# MIC.net
KiCad netlist of a schematic drawn in EasyEDA Pro
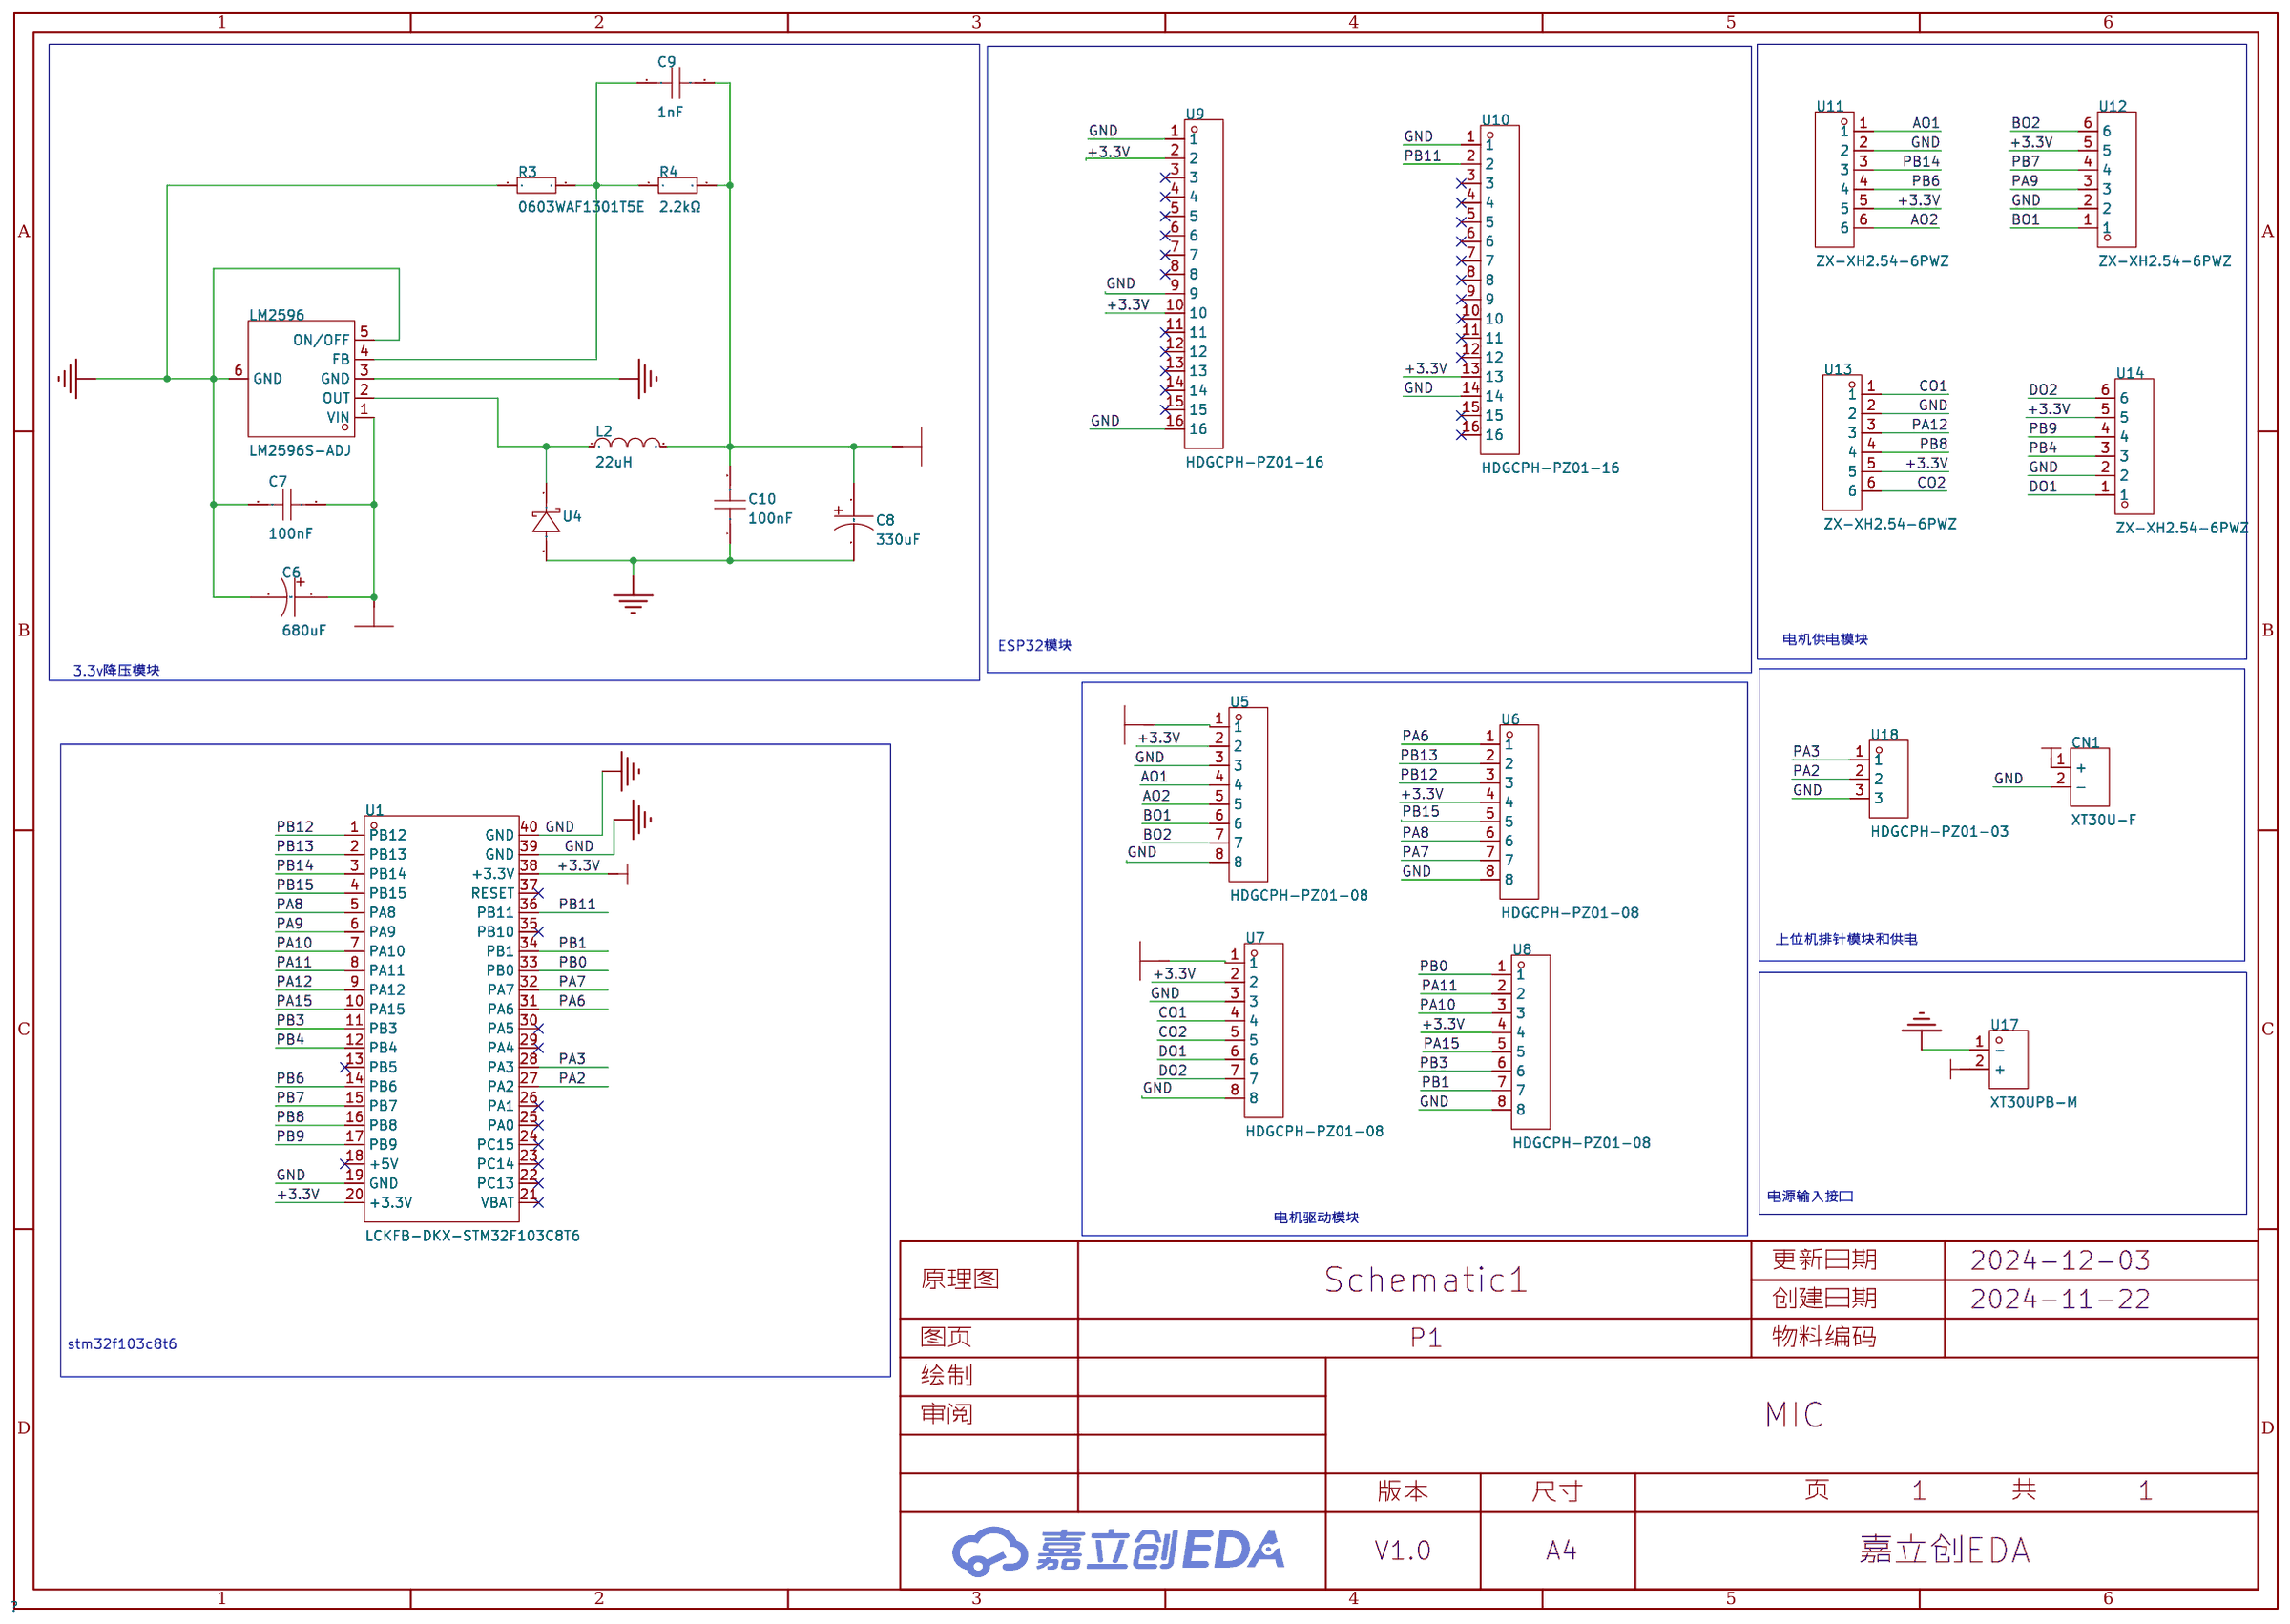
[diagram p0: schematic sheet]

(export (version "E")
  (design (tool "Eeschema 10.0.6"))
  (components
    (comp (ref "C6")
      (value "680uF")
      (footprint "easyedapro:CAP-TH_BD10.0-P5.00-D1.0-FD")
      (fields (field (name "Manufacturer Part") "LKME1601V681MF") (field (name "Manufacturer") "Ymin(永铭)"))
      (libsource (lib "easyedapro") (part "LKME1601V681MF"))
    )
    (comp (ref "C7")
      (value "100nF")
      (footprint "easyedapro:C0805")
      (fields
        (field (name "Manufacturer Part") "CC0805KKX7R0BB104")
        (field (name "Manufacturer") "YAGEO(国巨)")
      )
      (libsource (lib "easyedapro") (part "CapAcitance"))
    )
    (comp (ref "C8")
      (value "330uF")
      (footprint "easyedapro:CAP-TH_BD10.0-P5.00-D1.0-FD")
      (fields (field (name "Manufacturer Part") "ERE1HM331G16OT") (field (name "Manufacturer") "AISHI(艾华集团)"))
      (libsource (lib "easyedapro") (part "LKME1601V681MF"))
    )
    (comp (ref "C9")
      (value "1nF")
      (footprint "easyedapro:C0805")
      (fields
        (field (name "Manufacturer Part") "CL10B102KB8NNNC")
        (field (name "Manufacturer") "SAMSUNG(三星)")
      )
      (libsource (lib "easyedapro") (part "CapAcitance"))
    )
    (comp (ref "C10")
      (value "100nF")
      (footprint "easyedapro:C0805")
      (fields
        (field (name "Manufacturer Part") "CC0603KRX7R9BB104")
        (field (name "Manufacturer") "YAGEO(国巨)")
      )
      (libsource (lib "easyedapro") (part "CapAcitance"))
    )
    (comp (ref "CN1")
      (value "XT30U-F")
      (footprint "easyedapro:CONN-TH_XT30UPB-F")
      (description "类别:-;类型1:-;")
      (fields (field (name "Manufacturer") "AMASS(艾迈斯)"))
      (libsource (lib "easyedapro") (part "XT30UPB-F"))
    )
    (comp (ref "L2")
      (value "22uH")
      (footprint "easyedapro:IND-SMD_L7.0-W6.6_FXL0630")
      (description "电感值:22uH;精度:±20%;额定电流:2.5A;饱和电流(Isat):3A;类型:一体成型电感;")
      (fields (field (name "Manufacturer Part") "SMMS0630-220M") (field (name "Manufacturer") "SXN(顺翔诺)"))
      (libsource (lib "easyedapro") (part "FXL0630-220-M"))
    )
    (comp (ref "LM2596")
      (value "LM2596S-ADJ")
      (footprint "easyedapro:TO-263-5_L10.0-W8.4-P1.70-LS15.3-BR")
      (description "功能类型:降压型;输出类型:可调;输入电压:40V;输出电压:1.23V~37V;输出电流(最大值):3.5A;")
      (fields (field (name "Manufacturer") "HXY MOSFET(华轩阳电子)"))
      (libsource (lib "easyedapro") (part "LM2596S-ADJ_C5349987"))
    )
    (comp (ref "R3")
      (value "0603WAF1301T5E")
      (footprint "easyedapro:R0603")
      (fields (field (name "Manufacturer") "UNI-ROYAL(厚声)"))
      (libsource (lib "easyedapro") (part "电阻"))
    )
    (comp (ref "R4")
      (value "2.2kΩ")
      (footprint "easyedapro:R0603")
      (fields (field (name "Manufacturer Part") "RC0603JR-072K2L") (field (name "Manufacturer") "YAGEO(国巨)"))
      (libsource (lib "easyedapro") (part "电阻"))
    )
    (comp (ref "U1")
      (value "LCKFB-DKX-STM32F103C8T6")
      (footprint "easyedapro:CONN-TH_L53.3-W22.9_STM32F103C8T6-CARD")
      (fields (field (name "Manufacturer") "立创开发板"))
      (libsource (lib "easyedapro") (part "LCKFB-DKX-STM32F103C8T6"))
    )
    (comp (ref "U4")
      (value "CDBC540-G")
      (footprint "easyedapro:SMC_L6.9-W5.9-LS7.9-RD")
      (description "正向压降(Vf):550mV@5A;直流反向耐压(Vr):40V;平均整流电流(Io):5A;")
      (fields (field (name "Manufacturer") "Comchip(典琦)"))
      (libsource (lib "easyedapro") (part "cdbc540-g"))
    )
    (comp (ref "U5")
      (value "HDGCPH-PZ01-08")
      (footprint "easyedapro:HDR-TH_8P-P2.54-V-M")
      (fields (field (name "Manufacturer") "HDGC(华德共创)"))
      (libsource (lib "easyedapro") (part "HDGCPH-PZ01- 08"))
    )
    (comp (ref "U6")
      (value "HDGCPH-PZ01-08")
      (footprint "easyedapro:HDR-TH_8P-P2.54-V-M")
      (fields (field (name "Manufacturer") "HDGC(华德共创)"))
      (libsource (lib "easyedapro") (part "HDGCPH-PZ01- 08"))
    )
    (comp (ref "U7")
      (value "HDGCPH-PZ01-08")
      (footprint "easyedapro:HDR-TH_8P-P2.54-V-M")
      (fields (field (name "Manufacturer") "HDGC(华德共创)"))
      (libsource (lib "easyedapro") (part "HDGCPH-PZ01- 08"))
    )
    (comp (ref "U8")
      (value "HDGCPH-PZ01-08")
      (footprint "easyedapro:HDR-TH_8P-P2.54-V-M")
      (fields (field (name "Manufacturer") "HDGC(华德共创)"))
      (libsource (lib "easyedapro") (part "HDGCPH-PZ01- 08"))
    )
    (comp (ref "U9")
      (value "HDGCPH-PZ01-16")
      (footprint "easyedapro:HDR-TH_16P-P2.54-V-M_1")
      (fields (field (name "Manufacturer") "HDGC(华德共创)"))
      (libsource (lib "easyedapro") (part "HDGCPH-PZ01-16"))
    )
    (comp (ref "U10")
      (value "HDGCPH-PZ01-16")
      (footprint "easyedapro:HDR-TH_16P-P2.54-V-M_1")
      (fields (field (name "Manufacturer") "HDGC(华德共创)"))
      (libsource (lib "easyedapro") (part "HDGCPH-PZ01-16"))
    )
    (comp (ref "U11")
      (value "ZX-XH2.54-6PWZ")
      (footprint "easyedapro:CONN-TH_6P-P2.50_ZX-XH2.54-6PWZ")
      (fields (field (name "Manufacturer") "Megastar(兆星)"))
      (libsource (lib "easyedapro") (part "ZX-XH2.54-6PWZ"))
    )
    (comp (ref "U12")
      (value "ZX-XH2.54-6PWZ")
      (footprint "easyedapro:CONN-TH_6P-P2.50_ZX-XH2.54-6PWZ")
      (fields (field (name "Manufacturer") "Megastar(兆星)"))
      (libsource (lib "easyedapro") (part "ZX-XH2.54-6PWZ"))
    )
    (comp (ref "U13")
      (value "ZX-XH2.54-6PWZ")
      (footprint "easyedapro:CONN-TH_6P-P2.50_ZX-XH2.54-6PWZ")
      (fields (field (name "Manufacturer") "Megastar(兆星)"))
      (libsource (lib "easyedapro") (part "ZX-XH2.54-6PWZ"))
    )
    (comp (ref "U14")
      (value "ZX-XH2.54-6PWZ")
      (footprint "easyedapro:CONN-TH_6P-P2.50_ZX-XH2.54-6PWZ")
      (fields (field (name "Manufacturer") "Megastar(兆星)"))
      (libsource (lib "easyedapro") (part "ZX-XH2.54-6PWZ"))
    )
    (comp (ref "U17")
      (value "XT30UPB-M")
      (footprint "easyedapro:CONN-TH_XT30U-F")
      (description "类别:-;类型1:-;")
      (fields (field (name "Manufacturer") "AMASS(艾迈斯)"))
      (libsource (lib "easyedapro") (part "XT30U-F"))
    )
    (comp (ref "U18")
      (value "HDGCPH-PZ01-03")
      (footprint "easyedapro:HDR-TH_3P-P2.54-V-M-3")
      (fields (field (name "Manufacturer") "HDGC(华德共创)"))
      (libsource (lib "easyedapro") (part "HDGCPH-PZ01-03"))
    )
  )
  (nets
    (net (code "1") (name "+3.3V") (class "Default")
      (node (ref "C10") (pin "2") (pinfunction "2_2") (pintype "input"))
      (node (ref "C8") (pin "1") (pinfunction "1_1") (pintype "input"))
      (node (ref "C9") (pin "2") (pinfunction "2_2") (pintype "input"))
      (node (ref "L2") (pin "2") (pinfunction "2_2") (pintype "unspecified"))
      (node (ref "R4") (pin "2") (pinfunction "2_2") (pintype "input"))
      (node (ref "U1") (pin "20") (pinfunction "+3.3V_20") (pintype "unspecified"))
      (node (ref "U1") (pin "38") (pinfunction "+3.3V_38") (pintype "unspecified"))
      (node (ref "U10") (pin "13") (pinfunction "13_13") (pintype "unspecified"))
      (node (ref "U11") (pin "5") (pinfunction "5_5") (pintype "unspecified"))
      (node (ref "U12") (pin "5") (pinfunction "5_5") (pintype "unspecified"))
      (node (ref "U13") (pin "5") (pinfunction "5_5") (pintype "unspecified"))
      (node (ref "U14") (pin "5") (pinfunction "5_5") (pintype "unspecified"))
      (node (ref "U5") (pin "2") (pinfunction "2_2") (pintype "unspecified"))
      (node (ref "U6") (pin "4") (pinfunction "4_4") (pintype "unspecified"))
      (node (ref "U7") (pin "2") (pinfunction "2_2") (pintype "unspecified"))
      (node (ref "U8") (pin "4") (pinfunction "4_4") (pintype "unspecified"))
      (node (ref "U9") (pin "10") (pinfunction "10_10") (pintype "unspecified"))
      (node (ref "U9") (pin "2") (pinfunction "2_2") (pintype "unspecified"))
    )
    (net (code "2") (name "+12V") (class "Default")
      (node (ref "C6") (pin "1") (pinfunction "1_1") (pintype "input"))
      (node (ref "C7") (pin "2") (pinfunction "2_2") (pintype "input"))
      (node (ref "CN1") (pin "1") (pinfunction "+_1") (pintype "unspecified"))
      (node (ref "LM2596") (pin "1") (pinfunction "VIN_1") (pintype "unspecified"))
      (node (ref "U17") (pin "2") (pinfunction "+_2") (pintype "unspecified"))
      (node (ref "U5") (pin "1") (pinfunction "1_1") (pintype "unspecified"))
      (node (ref "U7") (pin "1") (pinfunction "1_1") (pintype "unspecified"))
    )
    (net (code "3") (name "/AO1") (class "Default")
      (node (ref "U11") (pin "1") (pinfunction "1_1") (pintype "unspecified"))
      (node (ref "U5") (pin "4") (pinfunction "4_4") (pintype "unspecified"))
    )
    (net (code "4") (name "/AO2") (class "Default")
      (node (ref "U11") (pin "6") (pinfunction "6_6") (pintype "unspecified"))
      (node (ref "U5") (pin "5") (pinfunction "5_5") (pintype "unspecified"))
    )
    (net (code "5") (name "/BO1") (class "Default")
      (node (ref "U12") (pin "1") (pinfunction "1_1") (pintype "unspecified"))
      (node (ref "U5") (pin "6") (pinfunction "6_6") (pintype "unspecified"))
    )
    (net (code "6") (name "/BO2") (class "Default")
      (node (ref "U12") (pin "6") (pinfunction "6_6") (pintype "unspecified"))
      (node (ref "U5") (pin "7") (pinfunction "7_7") (pintype "unspecified"))
    )
    (net (code "7") (name "/CO1") (class "Default")
      (node (ref "U13") (pin "1") (pinfunction "1_1") (pintype "unspecified"))
      (node (ref "U7") (pin "4") (pinfunction "4_4") (pintype "unspecified"))
    )
    (net (code "8") (name "/CO2") (class "Default")
      (node (ref "U13") (pin "6") (pinfunction "6_6") (pintype "unspecified"))
      (node (ref "U7") (pin "5") (pinfunction "5_5") (pintype "unspecified"))
    )
    (net (code "9") (name "/DO1") (class "Default")
      (node (ref "U14") (pin "1") (pinfunction "1_1") (pintype "unspecified"))
      (node (ref "U7") (pin "6") (pinfunction "6_6") (pintype "unspecified"))
    )
    (net (code "10") (name "/DO2") (class "Default")
      (node (ref "U14") (pin "6") (pinfunction "6_6") (pintype "unspecified"))
      (node (ref "U7") (pin "7") (pinfunction "7_7") (pintype "unspecified"))
    )
    (net (code "11") (name "/PA2") (class "Default")
      (node (ref "U1") (pin "27") (pinfunction "PA2_27") (pintype "unspecified"))
      (node (ref "U18") (pin "2") (pinfunction "2_2") (pintype "unspecified"))
    )
    (net (code "12") (name "/PA3") (class "Default")
      (node (ref "U1") (pin "28") (pinfunction "PA3_28") (pintype "unspecified"))
      (node (ref "U18") (pin "1") (pinfunction "1_1") (pintype "unspecified"))
    )
    (net (code "13") (name "/PA6") (class "Default")
      (node (ref "U1") (pin "31") (pinfunction "PA6_31") (pintype "unspecified"))
      (node (ref "U6") (pin "1") (pinfunction "1_1") (pintype "unspecified"))
    )
    (net (code "14") (name "/PA7") (class "Default")
      (node (ref "U1") (pin "32") (pinfunction "PA7_32") (pintype "unspecified"))
      (node (ref "U6") (pin "7") (pinfunction "7_7") (pintype "unspecified"))
    )
    (net (code "15") (name "/PA8") (class "Default")
      (node (ref "U1") (pin "5") (pinfunction "PA8_5") (pintype "unspecified"))
      (node (ref "U6") (pin "6") (pinfunction "6_6") (pintype "unspecified"))
    )
    (net (code "16") (name "/PA9") (class "Default")
      (node (ref "U1") (pin "6") (pinfunction "PA9_6") (pintype "unspecified"))
      (node (ref "U12") (pin "3") (pinfunction "3_3") (pintype "unspecified"))
    )
    (net (code "17") (name "/PA10") (class "Default")
      (node (ref "U1") (pin "7") (pinfunction "PA10_7") (pintype "unspecified"))
      (node (ref "U8") (pin "3") (pinfunction "3_3") (pintype "unspecified"))
    )
    (net (code "18") (name "/PA11") (class "Default")
      (node (ref "U1") (pin "8") (pinfunction "PA11_8") (pintype "unspecified"))
      (node (ref "U8") (pin "2") (pinfunction "2_2") (pintype "unspecified"))
    )
    (net (code "19") (name "/PA12") (class "Default")
      (node (ref "U1") (pin "9") (pinfunction "PA12_9") (pintype "unspecified"))
      (node (ref "U13") (pin "3") (pinfunction "3_3") (pintype "unspecified"))
    )
    (net (code "20") (name "/PA15") (class "Default")
      (node (ref "U1") (pin "10") (pinfunction "PA15_10") (pintype "unspecified"))
      (node (ref "U8") (pin "5") (pinfunction "5_5") (pintype "unspecified"))
    )
    (net (code "21") (name "/PB0") (class "Default")
      (node (ref "U1") (pin "33") (pinfunction "PB0_33") (pintype "unspecified"))
      (node (ref "U8") (pin "1") (pinfunction "1_1") (pintype "unspecified"))
    )
    (net (code "22") (name "/PB1") (class "Default")
      (node (ref "U1") (pin "34") (pinfunction "PB1_34") (pintype "unspecified"))
      (node (ref "U8") (pin "7") (pinfunction "7_7") (pintype "unspecified"))
    )
    (net (code "23") (name "/PB3") (class "Default")
      (node (ref "U1") (pin "11") (pinfunction "PB3_11") (pintype "unspecified"))
      (node (ref "U8") (pin "6") (pinfunction "6_6") (pintype "unspecified"))
    )
    (net (code "24") (name "/PB4") (class "Default")
      (node (ref "U1") (pin "12") (pinfunction "PB4_12") (pintype "unspecified"))
      (node (ref "U14") (pin "3") (pinfunction "3_3") (pintype "unspecified"))
    )
    (net (code "25") (name "/PB6") (class "Default")
      (node (ref "U1") (pin "14") (pinfunction "PB6_14") (pintype "unspecified"))
      (node (ref "U11") (pin "4") (pinfunction "4_4") (pintype "unspecified"))
    )
    (net (code "26") (name "/PB7") (class "Default")
      (node (ref "U1") (pin "15") (pinfunction "PB7_15") (pintype "unspecified"))
      (node (ref "U12") (pin "4") (pinfunction "4_4") (pintype "unspecified"))
    )
    (net (code "27") (name "/PB8") (class "Default")
      (node (ref "U1") (pin "16") (pinfunction "PB8_16") (pintype "unspecified"))
      (node (ref "U13") (pin "4") (pinfunction "4_4") (pintype "unspecified"))
    )
    (net (code "28") (name "/PB9") (class "Default")
      (node (ref "U1") (pin "17") (pinfunction "PB9_17") (pintype "unspecified"))
      (node (ref "U14") (pin "4") (pinfunction "4_4") (pintype "unspecified"))
    )
    (net (code "29") (name "/PB11") (class "Default")
      (node (ref "U1") (pin "36") (pinfunction "PB11_36") (pintype "unspecified"))
      (node (ref "U10") (pin "2") (pinfunction "2_2") (pintype "unspecified"))
    )
    (net (code "30") (name "/PB12") (class "Default")
      (node (ref "U1") (pin "1") (pinfunction "PB12_1") (pintype "unspecified"))
      (node (ref "U6") (pin "3") (pinfunction "3_3") (pintype "unspecified"))
    )
    (net (code "31") (name "/PB13") (class "Default")
      (node (ref "U1") (pin "2") (pinfunction "PB13_2") (pintype "unspecified"))
      (node (ref "U6") (pin "2") (pinfunction "2_2") (pintype "unspecified"))
    )
    (net (code "32") (name "/PB14") (class "Default")
      (node (ref "U1") (pin "3") (pinfunction "PB14_3") (pintype "unspecified"))
      (node (ref "U11") (pin "3") (pinfunction "3_3") (pintype "unspecified"))
    )
    (net (code "33") (name "/PB15") (class "Default")
      (node (ref "U1") (pin "4") (pinfunction "PB15_4") (pintype "unspecified"))
      (node (ref "U6") (pin "5") (pinfunction "5_5") (pintype "unspecified"))
    )
    (net (code "34") (name "GND") (class "Default")
      (node (ref "C10") (pin "1") (pinfunction "1_1") (pintype "input"))
      (node (ref "C6") (pin "2") (pinfunction "2_2") (pintype "input"))
      (node (ref "C7") (pin "1") (pinfunction "1_1") (pintype "input"))
      (node (ref "C8") (pin "2") (pinfunction "2_2") (pintype "input"))
      (node (ref "CN1") (pin "2") (pinfunction "-_2") (pintype "unspecified"))
      (node (ref "LM2596") (pin "3") (pinfunction "GND_3") (pintype "unspecified"))
      (node (ref "LM2596") (pin "5") (pinfunction "ON/OFF_5") (pintype "unspecified"))
      (node (ref "LM2596") (pin "6") (pinfunction "GND_6") (pintype "unspecified"))
      (node (ref "R3") (pin "1") (pinfunction "1_1") (pintype "input"))
      (node (ref "U1") (pin "19") (pinfunction "GND_19") (pintype "unspecified"))
      (node (ref "U1") (pin "39") (pinfunction "GND_39") (pintype "unspecified"))
      (node (ref "U1") (pin "40") (pinfunction "GND_40") (pintype "unspecified"))
      (node (ref "U10") (pin "1") (pinfunction "1_1") (pintype "unspecified"))
      (node (ref "U10") (pin "14") (pinfunction "14_14") (pintype "unspecified"))
      (node (ref "U11") (pin "2") (pinfunction "2_2") (pintype "unspecified"))
      (node (ref "U12") (pin "2") (pinfunction "2_2") (pintype "unspecified"))
      (node (ref "U13") (pin "2") (pinfunction "2_2") (pintype "unspecified"))
      (node (ref "U14") (pin "2") (pinfunction "2_2") (pintype "unspecified"))
      (node (ref "U17") (pin "1") (pinfunction "-_1") (pintype "unspecified"))
      (node (ref "U18") (pin "3") (pinfunction "3_3") (pintype "unspecified"))
      (node (ref "U4") (pin "2") (pinfunction "2_2") (pintype "unspecified"))
      (node (ref "U5") (pin "3") (pinfunction "3_3") (pintype "unspecified"))
      (node (ref "U5") (pin "8") (pinfunction "8_8") (pintype "unspecified"))
      (node (ref "U6") (pin "8") (pinfunction "8_8") (pintype "unspecified"))
      (node (ref "U7") (pin "3") (pinfunction "3_3") (pintype "unspecified"))
      (node (ref "U7") (pin "8") (pinfunction "8_8") (pintype "unspecified"))
      (node (ref "U8") (pin "8") (pinfunction "8_8") (pintype "unspecified"))
      (node (ref "U9") (pin "1") (pinfunction "1_1") (pintype "unspecified"))
      (node (ref "U9") (pin "16") (pinfunction "16_16") (pintype "unspecified"))
      (node (ref "U9") (pin "9") (pinfunction "9_9") (pintype "unspecified"))
    )
    (net (code "35") (name "Net-(LM2596-FB)") (class "Default")
      (node (ref "C9") (pin "1") (pinfunction "1_1") (pintype "input"))
      (node (ref "LM2596") (pin "4") (pinfunction "FB_4") (pintype "unspecified"))
      (node (ref "R3") (pin "2") (pinfunction "2_2") (pintype "input"))
      (node (ref "R4") (pin "1") (pinfunction "1_1") (pintype "input"))
    )
    (net (code "36") (name "Net-(LM2596-OUT)") (class "Default")
      (node (ref "L2") (pin "1") (pinfunction "1_1") (pintype "unspecified"))
      (node (ref "LM2596") (pin "2") (pinfunction "OUT_2") (pintype "unspecified"))
      (node (ref "U4") (pin "1") (pinfunction "1_1") (pintype "unspecified"))
    )
    (net (code "37") (name "unconnected-(U1-+5V-Pad18)") (class "Default")
      (node (ref "U1") (pin "18") (pinfunction "+5V_18") (pintype "unspecified+no_connect"))
    )
    (net (code "38") (name "unconnected-(U1-PA0-Pad25)") (class "Default")
      (node (ref "U1") (pin "25") (pinfunction "PA0_25") (pintype "unspecified+no_connect"))
    )
    (net (code "39") (name "unconnected-(U1-PA1-Pad26)") (class "Default")
      (node (ref "U1") (pin "26") (pinfunction "PA1_26") (pintype "unspecified+no_connect"))
    )
    (net (code "40") (name "unconnected-(U1-PA4-Pad29)") (class "Default")
      (node (ref "U1") (pin "29") (pinfunction "PA4_29") (pintype "unspecified+no_connect"))
    )
    (net (code "41") (name "unconnected-(U1-PA5-Pad30)") (class "Default")
      (node (ref "U1") (pin "30") (pinfunction "PA5_30") (pintype "unspecified+no_connect"))
    )
    (net (code "42") (name "unconnected-(U1-PB5-Pad13)") (class "Default")
      (node (ref "U1") (pin "13") (pinfunction "PB5_13") (pintype "unspecified+no_connect"))
    )
    (net (code "43") (name "unconnected-(U1-PB10-Pad35)") (class "Default")
      (node (ref "U1") (pin "35") (pinfunction "PB10_35") (pintype "unspecified+no_connect"))
    )
    (net (code "44") (name "unconnected-(U1-PC13-Pad22)") (class "Default")
      (node (ref "U1") (pin "22") (pinfunction "PC13_22") (pintype "unspecified+no_connect"))
    )
    (net (code "45") (name "unconnected-(U1-PC14-Pad23)") (class "Default")
      (node (ref "U1") (pin "23") (pinfunction "PC14_23") (pintype "unspecified+no_connect"))
    )
    (net (code "46") (name "unconnected-(U1-PC15-Pad24)") (class "Default")
      (node (ref "U1") (pin "24") (pinfunction "PC15_24") (pintype "unspecified+no_connect"))
    )
    (net (code "47") (name "unconnected-(U1-RESET-Pad37)") (class "Default")
      (node (ref "U1") (pin "37") (pinfunction "RESET_37") (pintype "unspecified+no_connect"))
    )
    (net (code "48") (name "unconnected-(U1-VBAT-Pad21)") (class "Default")
      (node (ref "U1") (pin "21") (pinfunction "VBAT_21") (pintype "unspecified+no_connect"))
    )
    (net (code "49") (name "unconnected-(U9-Pad3)") (class "Default")
      (node (ref "U9") (pin "3") (pinfunction "3_3") (pintype "unspecified+no_connect"))
    )
    (net (code "50") (name "unconnected-(U9-Pad4)") (class "Default")
      (node (ref "U9") (pin "4") (pinfunction "4_4") (pintype "unspecified+no_connect"))
    )
    (net (code "51") (name "unconnected-(U9-Pad5)") (class "Default")
      (node (ref "U9") (pin "5") (pinfunction "5_5") (pintype "unspecified+no_connect"))
    )
    (net (code "52") (name "unconnected-(U9-Pad6)") (class "Default")
      (node (ref "U9") (pin "6") (pinfunction "6_6") (pintype "unspecified+no_connect"))
    )
    (net (code "53") (name "unconnected-(U9-Pad7)") (class "Default")
      (node (ref "U9") (pin "7") (pinfunction "7_7") (pintype "unspecified+no_connect"))
    )
    (net (code "54") (name "unconnected-(U9-Pad8)") (class "Default")
      (node (ref "U9") (pin "8") (pinfunction "8_8") (pintype "unspecified+no_connect"))
    )
    (net (code "55") (name "unconnected-(U9-Pad11)") (class "Default")
      (node (ref "U9") (pin "11") (pinfunction "11_11") (pintype "unspecified+no_connect"))
    )
    (net (code "56") (name "unconnected-(U9-Pad12)") (class "Default")
      (node (ref "U9") (pin "12") (pinfunction "12_12") (pintype "unspecified+no_connect"))
    )
    (net (code "57") (name "unconnected-(U9-Pad13)") (class "Default")
      (node (ref "U9") (pin "13") (pinfunction "13_13") (pintype "unspecified+no_connect"))
    )
    (net (code "58") (name "unconnected-(U9-Pad14)") (class "Default")
      (node (ref "U9") (pin "14") (pinfunction "14_14") (pintype "unspecified+no_connect"))
    )
    (net (code "59") (name "unconnected-(U9-Pad15)") (class "Default")
      (node (ref "U9") (pin "15") (pinfunction "15_15") (pintype "unspecified+no_connect"))
    )
    (net (code "60") (name "unconnected-(U10-Pad3)") (class "Default")
      (node (ref "U10") (pin "3") (pinfunction "3_3") (pintype "unspecified+no_connect"))
    )
    (net (code "61") (name "unconnected-(U10-Pad4)") (class "Default")
      (node (ref "U10") (pin "4") (pinfunction "4_4") (pintype "unspecified+no_connect"))
    )
    (net (code "62") (name "unconnected-(U10-Pad5)") (class "Default")
      (node (ref "U10") (pin "5") (pinfunction "5_5") (pintype "unspecified+no_connect"))
    )
    (net (code "63") (name "unconnected-(U10-Pad6)") (class "Default")
      (node (ref "U10") (pin "6") (pinfunction "6_6") (pintype "unspecified+no_connect"))
    )
    (net (code "64") (name "unconnected-(U10-Pad7)") (class "Default")
      (node (ref "U10") (pin "7") (pinfunction "7_7") (pintype "unspecified+no_connect"))
    )
    (net (code "65") (name "unconnected-(U10-Pad8)") (class "Default")
      (node (ref "U10") (pin "8") (pinfunction "8_8") (pintype "unspecified+no_connect"))
    )
    (net (code "66") (name "unconnected-(U10-Pad9)") (class "Default")
      (node (ref "U10") (pin "9") (pinfunction "9_9") (pintype "unspecified+no_connect"))
    )
    (net (code "67") (name "unconnected-(U10-Pad10)") (class "Default")
      (node (ref "U10") (pin "10") (pinfunction "10_10") (pintype "unspecified+no_connect"))
    )
    (net (code "68") (name "unconnected-(U10-Pad11)") (class "Default")
      (node (ref "U10") (pin "11") (pinfunction "11_11") (pintype "unspecified+no_connect"))
    )
    (net (code "69") (name "unconnected-(U10-Pad12)") (class "Default")
      (node (ref "U10") (pin "12") (pinfunction "12_12") (pintype "unspecified+no_connect"))
    )
    (net (code "70") (name "unconnected-(U10-Pad15)") (class "Default")
      (node (ref "U10") (pin "15") (pinfunction "15_15") (pintype "unspecified+no_connect"))
    )
    (net (code "71") (name "unconnected-(U10-Pad16)") (class "Default")
      (node (ref "U10") (pin "16") (pinfunction "16_16") (pintype "unspecified+no_connect"))
    )
  )
)
